# display.net
KiCad netlist of a schematic drawn in Altium Designer
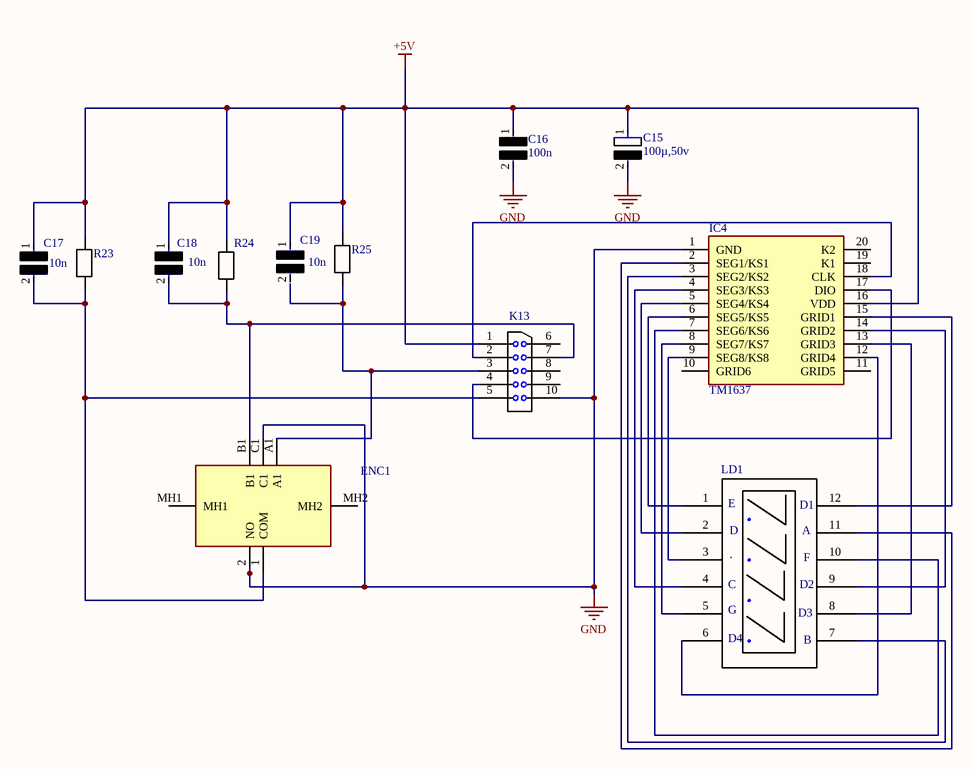
[diagram p0: display.SchDoc]

(export (version "E")
  (design (tool "Eeschema 10.0.6"))
  (components
    (comp (ref "C15")
      (value "100µ,50v")
      (footprint "RESC2013X50X30LL20T20")
      (description "CAP CER 0.1UF 10V X5R 0402")
      (fields (field (name "MANUFACTURER") "Kemet") (field (name "TOLERANCE") "0.1"))
      (libsource (lib "Schlib1") (part "Elektrolytische Capacitor"))
    )
    (comp (ref "C16")
      (value "100n")
      (footprint "RESC2013X50X30LL20T20")
      (libsource (lib "Schlib1") (part "Ceramische Capacitor"))
    )
    (comp (ref "C17")
      (value "10n")
      (footprint "RESC2013X50X30LL20T20")
      (libsource (lib "Schlib1") (part "Ceramische Capacitor"))
    )
    (comp (ref "C18")
      (value "10n")
      (footprint "RESC2013X50X30LL20T20")
      (libsource (lib "Schlib1") (part "Ceramische Capacitor"))
    )
    (comp (ref "C19")
      (value "10n")
      (footprint "RESC2013X50X30LL20T20")
      (libsource (lib "Schlib1") (part "Ceramische Capacitor"))
    )
    (comp (ref "ENC1")
      (value "Switch")
      (footprint "SamacSys:482009514001")
      (fields
        (field (name "MANUFACTURER_PART_NUMBER") "482009514001")
        (field (name "MOUSER PART NUMBER") "710-482009514001")
      )
      (libsource (lib "Schlib1") (part "Switch"))
    )
    (comp (ref "IC4")
      (value "TM1637")
      (footprint "SamacSys:DIP778W53P254L2612H431Q20N")
      (description "Integrated Circuit")
      (libsource (lib "Schlib1") (part "TM1637"))
    )
    (comp (ref "K13")
      (value "Pinheader,2rijig,10-polig")
      (footprint "PINHEADER, 2RIJIG,10-POLIG - duplicate - duplicate - duplicate")
      (libsource (lib "Schlib1") (part "Pinheader,2rijig,10-polig"))
    )
    (comp (ref "LD1")
      (value "7segdisplay")
      (footprint "7SEGDISPALY")
      (libsource (lib "Schlib1") (part "7segdisplay"))
    )
    (comp (ref "R23")
      (value "weerstand")
      (footprint "RESC2013X50X30LL20T20")
      (fields (field (name "MANUFACTURER") "Vishay Dale") (field (name "PART NUMBER") "CRCW08050000Z0EA"))
      (libsource (lib "Schlib1") (part "weerstand"))
    )
    (comp (ref "R24")
      (value "weerstand")
      (footprint "RESC2013X50X30LL20T20")
      (fields (field (name "MANUFACTURER") "Vishay Dale") (field (name "PART NUMBER") "CRCW08050000Z0EA"))
      (libsource (lib "Schlib1") (part "weerstand"))
    )
    (comp (ref "R25")
      (value "weerstand")
      (footprint "RESC2013X50X30LL20T20")
      (fields (field (name "MANUFACTURER") "Vishay Dale") (field (name "PART NUMBER") "CRCW08050000Z0EA"))
      (libsource (lib "Schlib1") (part "weerstand"))
    )
  )
  (nets
    (net (code "1") (name "+5V") (class "Default")
      (node (ref "C15") (pin "1") (pinfunction "1_1") (pintype "passive"))
      (node (ref "C16") (pin "1") (pinfunction "2_1") (pintype "passive"))
      (node (ref "C17") (pin "1") (pinfunction "2_1") (pintype "passive"))
      (node (ref "C18") (pin "1") (pinfunction "2_1") (pintype "passive"))
      (node (ref "C19") (pin "1") (pinfunction "2_1") (pintype "passive"))
      (node (ref "IC4") (pin "16") (pinfunction "VDD_16") (pintype "passive"))
      (node (ref "K13") (pin "1") (pintype "passive"))
      (node (ref "R23") (pin "2") (pinfunction "2_2") (pintype "passive"))
      (node (ref "R24") (pin "2") (pinfunction "2_2") (pintype "passive"))
      (node (ref "R25") (pin "2") (pinfunction "2_2") (pintype "passive"))
    )
    (net (code "2") (name "GND") (class "Default")
      (node (ref "C15") (pin "2") (pinfunction "2_2") (pintype "passive"))
      (node (ref "C16") (pin "2") (pinfunction "2_2") (pintype "passive"))
      (node (ref "ENC1") (pin "2") (pinfunction "NO_2") (pintype "passive"))
      (node (ref "ENC1") (pin "C1") (pinfunction "C1_C1") (pintype "passive"))
      (node (ref "IC4") (pin "1") (pinfunction "GND_1") (pintype "passive"))
      (node (ref "K13") (pin "10") (pintype "passive"))
    )
    (net (code "3") (name "Net-(C18-Pad2)") (class "Default")
      (node (ref "C18") (pin "2") (pinfunction "2_2") (pintype "passive"))
      (node (ref "ENC1") (pin "B1") (pinfunction "B1_B1") (pintype "passive"))
      (node (ref "K13") (pin "7") (pintype "passive"))
      (node (ref "R24") (pin "1") (pinfunction "1_1") (pintype "passive"))
    )
    (net (code "4") (name "Net-(ENC1-COM)") (class "Default")
      (node (ref "C17") (pin "2") (pinfunction "2_2") (pintype "passive"))
      (node (ref "ENC1") (pin "1") (pinfunction "COM_1") (pintype "passive"))
      (node (ref "K13") (pin "5") (pintype "passive"))
      (node (ref "R23") (pin "1") (pinfunction "1_1") (pintype "passive"))
    )
    (net (code "5") (name "Net-(ENC1-PadA1)") (class "Default")
      (node (ref "ENC1") (pin "A1") (pinfunction "A1_A1") (pintype "passive"))
      (node (ref "K13") (pin "3") (pintype "passive"))
      (node (ref "R25") (pin "1") (pinfunction "1_1") (pintype "passive"))
    )
    (net (code "6") (name "Net-(IC4-CLK)") (class "Default")
      (node (ref "IC4") (pin "18") (pinfunction "CLK_18") (pintype "passive"))
      (node (ref "K13") (pin "2") (pintype "passive"))
    )
    (net (code "7") (name "Net-(IC4-DIO)") (class "Default")
      (node (ref "IC4") (pin "17") (pinfunction "DIO_17") (pintype "passive"))
      (node (ref "K13") (pin "4") (pintype "passive"))
    )
    (net (code "8") (name "Net-(IC4-GRID1)") (class "Default")
      (node (ref "IC4") (pin "15") (pinfunction "GRID1_15") (pintype "passive"))
      (node (ref "LD1") (pin "12") (pinfunction "12_12") (pintype "passive"))
    )
    (net (code "9") (name "Net-(IC4-GRID2)") (class "Default")
      (node (ref "IC4") (pin "14") (pinfunction "GRID2_14") (pintype "passive"))
      (node (ref "LD1") (pin "9") (pinfunction "9_9") (pintype "passive"))
    )
    (net (code "10") (name "Net-(IC4-GRID3)") (class "Default")
      (node (ref "IC4") (pin "13") (pinfunction "GRID3_13") (pintype "passive"))
      (node (ref "LD1") (pin "8") (pinfunction "8_8") (pintype "passive"))
    )
    (net (code "11") (name "Net-(IC4-GRID4)") (class "Default")
      (node (ref "IC4") (pin "12") (pinfunction "GRID4_12") (pintype "passive"))
      (node (ref "LD1") (pin "6") (pinfunction "6_6") (pintype "passive"))
    )
    (net (code "12") (name "Net-(IC4-SEG1{slash}KS1)") (class "Default")
      (node (ref "IC4") (pin "2") (pinfunction "SEG1/KS1_2") (pintype "passive"))
      (node (ref "LD1") (pin "11") (pinfunction "11_11") (pintype "passive"))
    )
    (net (code "13") (name "Net-(IC4-SEG2{slash}KS2)") (class "Default")
      (node (ref "IC4") (pin "3") (pinfunction "SEG2/KS2_3") (pintype "passive"))
      (node (ref "LD1") (pin "7") (pinfunction "7_7") (pintype "passive"))
    )
    (net (code "14") (name "Net-(IC4-SEG3{slash}KS3)") (class "Default")
      (node (ref "IC4") (pin "4") (pinfunction "SEG3/KS3_4") (pintype "passive"))
      (node (ref "LD1") (pin "4") (pinfunction "4_4") (pintype "passive"))
    )
    (net (code "15") (name "Net-(IC4-SEG4{slash}KS4)") (class "Default")
      (node (ref "IC4") (pin "5") (pinfunction "SEG4/KS4_5") (pintype "passive"))
      (node (ref "LD1") (pin "2") (pinfunction "2_2") (pintype "passive"))
    )
    (net (code "16") (name "Net-(IC4-SEG5{slash}KS5)") (class "Default")
      (node (ref "IC4") (pin "6") (pinfunction "SEG5/KS5_6") (pintype "passive"))
      (node (ref "LD1") (pin "1") (pinfunction "1_1") (pintype "passive"))
    )
    (net (code "17") (name "Net-(IC4-SEG6{slash}KS6)") (class "Default")
      (node (ref "IC4") (pin "7") (pinfunction "SEG6/KS6_7") (pintype "passive"))
      (node (ref "LD1") (pin "10") (pinfunction "10_10") (pintype "passive"))
    )
    (net (code "18") (name "Net-(IC4-SEG7{slash}KS7)") (class "Default")
      (node (ref "IC4") (pin "8") (pinfunction "SEG7/KS7_8") (pintype "passive"))
      (node (ref "LD1") (pin "5") (pinfunction "5_5") (pintype "passive"))
    )
    (net (code "19") (name "Net-(IC4-SEG8{slash}KS8)") (class "Default")
      (node (ref "IC4") (pin "9") (pinfunction "SEG8/KS8_9") (pintype "passive"))
      (node (ref "LD1") (pin "3") (pinfunction "3_3") (pintype "passive"))
    )
    (net (code "20") (name "unconnected-(C19-Pad2)") (class "Default")
      (node (ref "C19") (pin "2") (pinfunction "2_2") (pintype "passive"))
    )
    (net (code "21") (name "unconnected-(ENC1-PadMH1)") (class "Default")
      (node (ref "ENC1") (pin "MH1") (pinfunction "MH1_MH1") (pintype "passive"))
    )
    (net (code "22") (name "unconnected-(ENC1-PadMH2)") (class "Default")
      (node (ref "ENC1") (pin "MH2") (pinfunction "MH2_MH2") (pintype "passive"))
    )
    (net (code "23") (name "unconnected-(IC4-GRID5-Pad11)") (class "Default")
      (node (ref "IC4") (pin "11") (pinfunction "GRID5_11") (pintype "passive"))
    )
    (net (code "24") (name "unconnected-(IC4-GRID6-Pad10)") (class "Default")
      (node (ref "IC4") (pin "10") (pinfunction "GRID6_10") (pintype "passive"))
    )
    (net (code "25") (name "unconnected-(IC4-K1-Pad19)") (class "Default")
      (node (ref "IC4") (pin "19") (pinfunction "K1_19") (pintype "passive"))
    )
    (net (code "26") (name "unconnected-(IC4-K2-Pad20)") (class "Default")
      (node (ref "IC4") (pin "20") (pinfunction "K2_20") (pintype "passive"))
    )
    (net (code "27") (name "unconnected-(K13-Pad6)") (class "Default")
      (node (ref "K13") (pin "6") (pintype "passive"))
    )
    (net (code "28") (name "unconnected-(K13-Pad8)") (class "Default")
      (node (ref "K13") (pin "8") (pintype "passive"))
    )
    (net (code "29") (name "unconnected-(K13-Pad9)") (class "Default")
      (node (ref "K13") (pin "9") (pintype "passive"))
    )
  )
)
